# LilyPad_Vibeboard.net
KiCad netlist of a schematic drawn in EAGLE
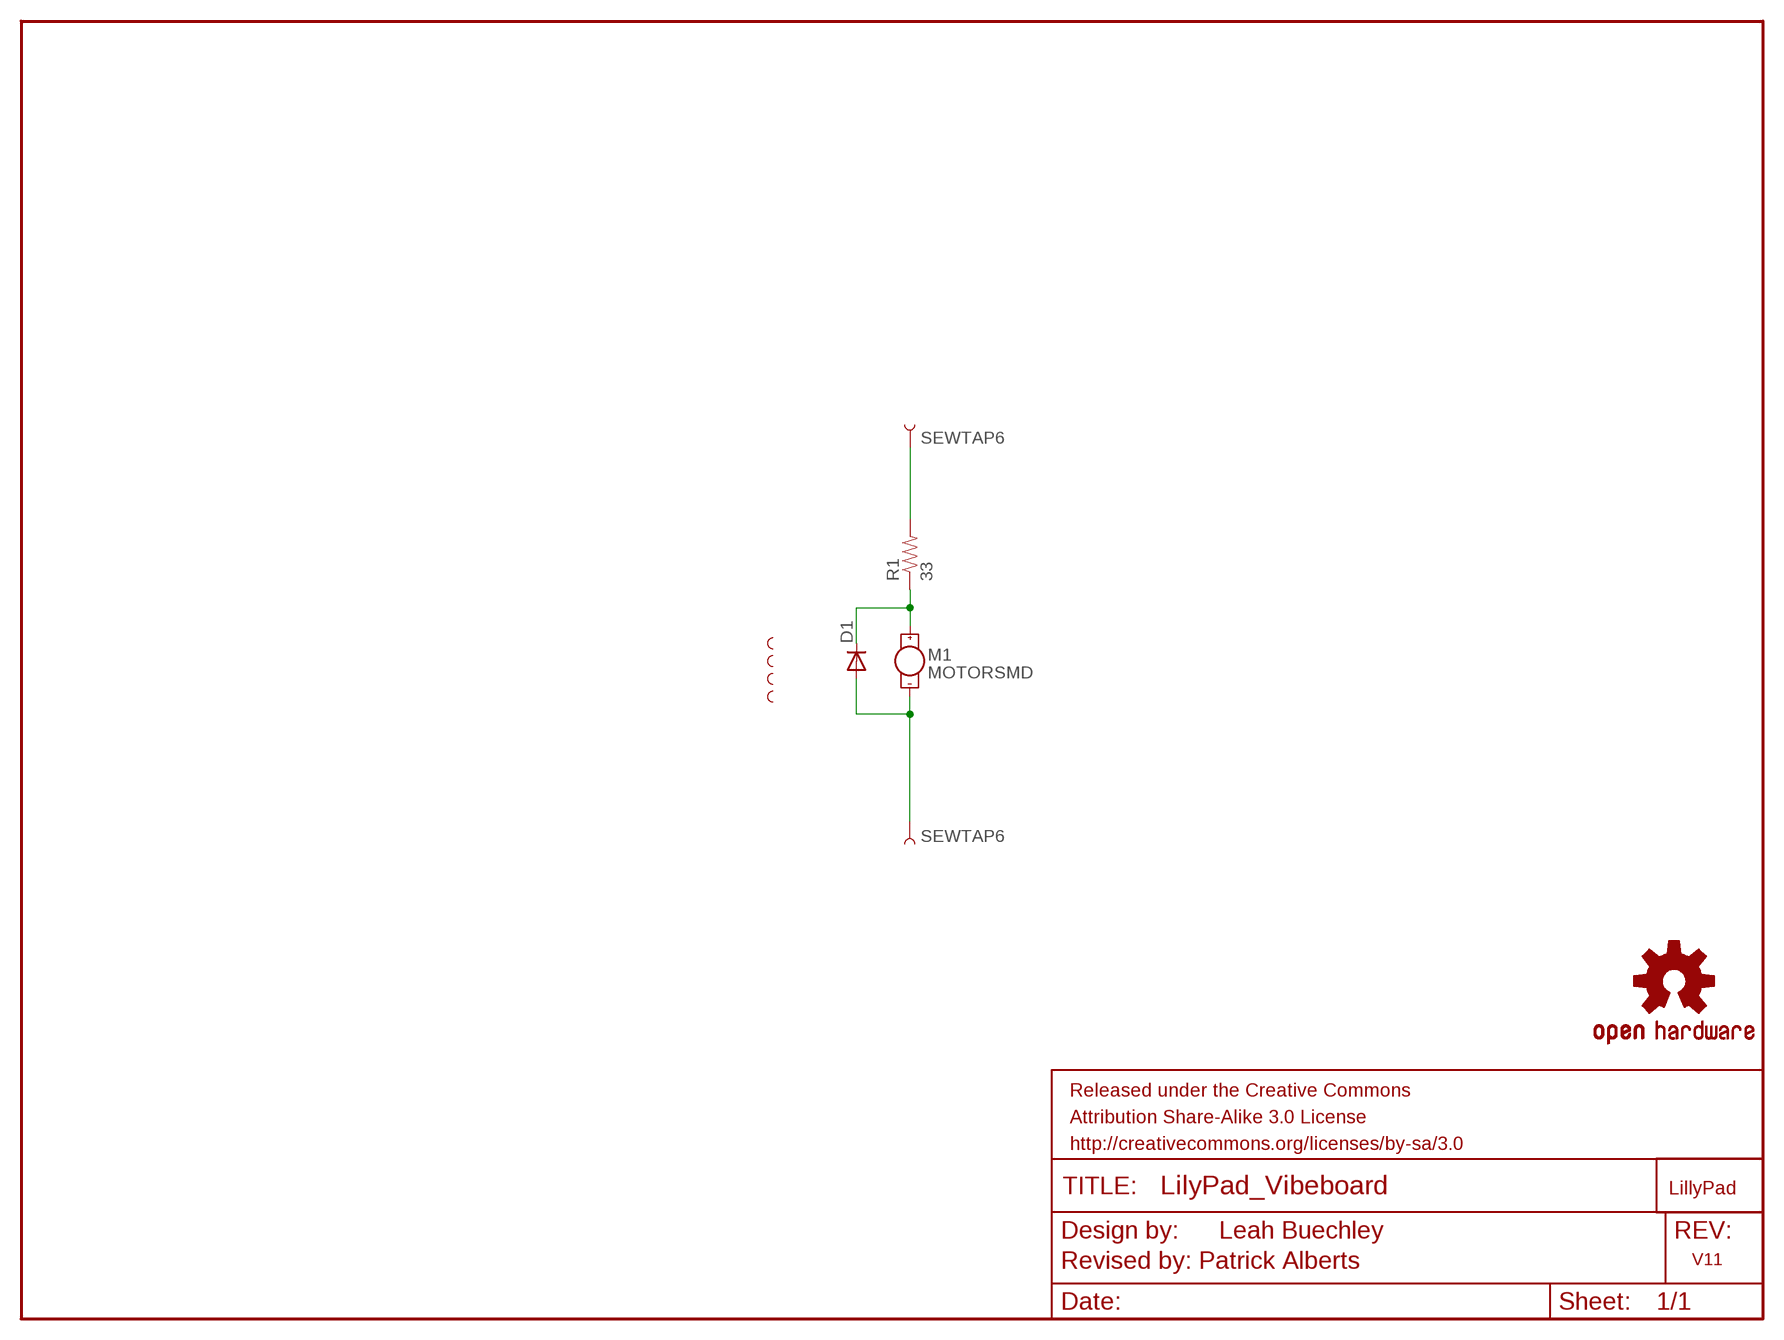
[diagram p0: schematic, sheet 1]

(export (version "E")
  (design (tool "Eeschema 10.0.6"))
  (components
    (comp (ref "D1")
      (value "DIODESOD")
      (footprint "eagle-import:SOD-323")
      (libsource (lib "eagle-import") (part "DIODESOD"))
    )
    (comp (ref "FRAME1")
      (value "FRAME-LETTER")
      (footprint "eagle-import:CREATIVE_COMMONS")
      (libsource (lib "eagle-import") (part "FRAME-LETTER"))
    )
    (comp (ref "LOGO1")
      (value "OSHW-LOGOS")
      (footprint "eagle-import:OSHW-LOGO-S")
      (libsource (lib "eagle-import") (part "OSHW-LOGOS"))
    )
    (comp (ref "M1")
      (value "MOTORSMD")
      (footprint "eagle-import:VIBE-MOTOR-10MM-SMD")
      (libsource (lib "eagle-import") (part "MOTORSMD"))
    )
    (comp (ref "R1")
      (value "33")
      (footprint "eagle-import:0603-RES")
      (libsource (lib "eagle-import") (part "33K-1%"))
    )
    (comp (ref "U$2")
      (value "LOGO-LPLP")
      (footprint "eagle-import:LOGO-LILYPAD")
      (libsource (lib "eagle-import") (part "LOGO-LPLP"))
    )
    (comp (ref "VIBE+")
      (value "SEWTAP6")
      (footprint "eagle-import:PETAL-SMALL-2SIDE")
      (libsource (lib "eagle-import") (part "SEWTAP6"))
    )
    (comp (ref "VIBE-")
      (value "SEWTAP6")
      (footprint "eagle-import:PETAL-SMALL-2SIDE")
      (libsource (lib "eagle-import") (part "SEWTAP6"))
    )
    (comp (ref "VIBE1")
      (value "SEWTAP-NOHOLE2")
      (footprint "eagle-import:PETAL-NOHOLE-2SIDE")
      (libsource (lib "eagle-import") (part "SEWTAP-NOHOLE2"))
    )
    (comp (ref "VIBE2")
      (value "SEWTAP-NOHOLEW-MASK")
      (footprint "eagle-import:PETAL-NOHOLE-2SIDE-SPECIAL-W-MASK")
      (libsource (lib "eagle-import") (part "SEWTAP-NOHOLEW-MASK"))
    )
    (comp (ref "VIBE3")
      (value "SEWTAP-NOHOLE2")
      (footprint "eagle-import:PETAL-NOHOLE-2SIDE")
      (libsource (lib "eagle-import") (part "SEWTAP-NOHOLE2"))
    )
    (comp (ref "VIBE4")
      (value "SEWTAP-NOHOLE2")
      (footprint "eagle-import:PETAL-NOHOLE-2SIDE")
      (libsource (lib "eagle-import") (part "SEWTAP-NOHOLE2"))
    )
  )
  (nets
    (net (code "1") (name "Net-(D1-A)") (class "Default")
      (node (ref "D1") (pin "2") (pinfunction "A_2") (pintype "passive"))
      (node (ref "M1") (pin "P$2") (pinfunction "-_P$2") (pintype "bidirectional"))
      (node (ref "VIBE-") (pin "1") (pinfunction "1_1") (pintype "bidirectional"))
    )
    (net (code "2") (name "Net-(D1-C)") (class "Default")
      (node (ref "D1") (pin "1") (pinfunction "C_1") (pintype "passive"))
      (node (ref "M1") (pin "P$1") (pinfunction "+_P$1") (pintype "bidirectional"))
      (node (ref "R1") (pin "1") (pinfunction "1_1") (pintype "passive"))
    )
    (net (code "3") (name "Net-(R1-Pad2)") (class "Default")
      (node (ref "R1") (pin "2") (pinfunction "2_2") (pintype "passive"))
      (node (ref "VIBE+") (pin "1") (pinfunction "1_1") (pintype "bidirectional"))
    )
  )
)
